# timer.net
KiCad netlist of a schematic drawn in EAGLE
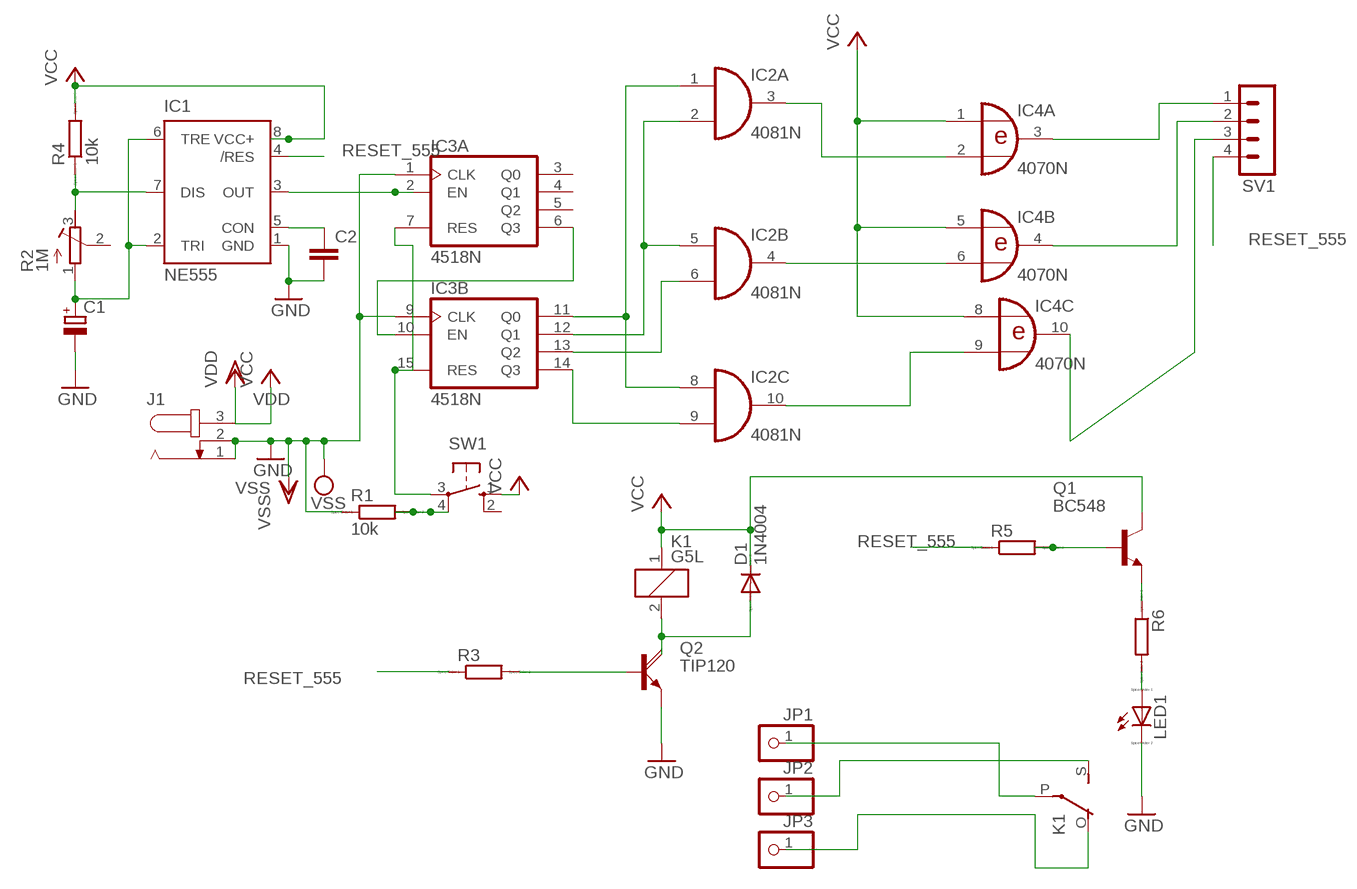
[diagram p0: schematic, sheet 1]

(export (version "E")
  (design (tool "Eeschema 10.0.6"))
  (components
    (comp (ref "C1")
      (value "CPOL-EUE2.5-6")
      (footprint "eagle-import:E2,5-6")
      (libsource (lib "eagle-import") (part "CPOL-EUE2.5-6"))
    )
    (comp (ref "C2")
      (value "C-EU025-024X044")
      (footprint "eagle-import:C025-024X044")
      (libsource (lib "eagle-import") (part "C-EU025-024X044"))
    )
    (comp (ref "D1")
      (value "1N4004")
      (footprint "eagle-import:DO41-10")
      (libsource (lib "eagle-import") (part "1N4004"))
    )
    (comp (ref "IC1")
      (value "NE555")
      (footprint "eagle-import:DIL-08")
      (fields (field (name "MF") "Arrow Electronics") (field (name "MPN") "NE555N"))
      (libsource (lib "eagle-import") (part "NE555"))
    )
    (comp (ref "IC2")
      (value "4081N")
      (footprint "eagle-import:DIL14")
      (libsource (lib "eagle-import") (part "4081N"))
    )
    (comp (ref "IC3")
      (value "4518N")
      (footprint "eagle-import:DIL16")
      (libsource (lib "eagle-import") (part "4518N"))
    )
    (comp (ref "IC4")
      (value "4070N")
      (footprint "eagle-import:DIL14")
      (libsource (lib "eagle-import") (part "4070N"))
    )
    (comp (ref "J1")
      (value "JACK-PLUG0")
      (footprint "eagle-import:SPC4077")
      (libsource (lib "eagle-import") (part "JACK-PLUG0"))
    )
    (comp (ref "JP1")
      (value "PINHD-1X1")
      (footprint "eagle-import:1X01")
      (libsource (lib "eagle-import") (part "PINHD-1X1"))
    )
    (comp (ref "JP2")
      (value "PINHD-1X1")
      (footprint "eagle-import:1X01")
      (libsource (lib "eagle-import") (part "PINHD-1X1"))
    )
    (comp (ref "JP3")
      (value "PINHD-1X1")
      (footprint "eagle-import:1X01")
      (libsource (lib "eagle-import") (part "PINHD-1X1"))
    )
    (comp (ref "K1")
      (value "G5L")
      (footprint "eagle-import:G5LE")
      (libsource (lib "eagle-import") (part "G5L"))
    )
    (comp (ref "LED1")
      (value "LED_ELD260")
      (footprint "eagle-import:LED_LD260")
      (libsource (lib "eagle-import") (part "LED_ELD260"))
    )
    (comp (ref "Q1")
      (value "BC548")
      (footprint "eagle-import:TO92-EBC")
      (libsource (lib "eagle-import") (part "BC548"))
    )
    (comp (ref "Q2")
      (value "TIP120")
      (footprint "eagle-import:TO220AH")
      (libsource (lib "eagle-import") (part "TIP120"))
    )
    (comp (ref "R1")
      (value "10k")
      (footprint "eagle-import:0207_10")
      (libsource (lib "eagle-import") (part "R0207/10"))
    )
    (comp (ref "R2")
      (value "1M")
      (footprint "eagle-import:RTRIM64W")
      (libsource (lib "eagle-import") (part "R-TRIMM64W"))
    )
    (comp (ref "R3")
      (value "R0207/10")
      (footprint "eagle-import:0207_10")
      (libsource (lib "eagle-import") (part "R0207/10"))
    )
    (comp (ref "R4")
      (value "10k")
      (footprint "eagle-import:0207_10")
      (libsource (lib "eagle-import") (part "R0207/10"))
    )
    (comp (ref "R5")
      (value "R0207/10")
      (footprint "eagle-import:0207_10")
      (libsource (lib "eagle-import") (part "R0207/10"))
    )
    (comp (ref "R6")
      (value "R0207/10")
      (footprint "eagle-import:0207_10")
      (libsource (lib "eagle-import") (part "R0207/10"))
    )
    (comp (ref "SV1")
      (value "MA04-1")
      (footprint "eagle-import:MA04-1")
      (libsource (lib "eagle-import") (part "MA04-1"))
    )
    (comp (ref "SW1")
      (value "10-XX")
      (footprint "eagle-import:B3F-10XX")
      (libsource (lib "eagle-import") (part "10-XX"))
    )
  )
  (nets
    (net (code "1") (name "/RESET_555") (class "Default")
      (node (ref "IC1") (pin "4") (pinfunction "/RES_4") (pintype "input"))
      (node (ref "R3") (pin "1") (pinfunction "1_1") (pintype "passive"))
      (node (ref "R5") (pin "1") (pinfunction "1_1") (pintype "passive"))
      (node (ref "SV1") (pin "4") (pinfunction "4_4") (pintype "passive"))
    )
    (net (code "2") (name "GND") (class "Default")
      (node (ref "C1") (pin "-") (pinfunction "-_-") (pintype "passive"))
      (node (ref "C2") (pin "2") (pinfunction "2_2") (pintype "passive"))
      (node (ref "IC1") (pin "1") (pinfunction "GND_1") (pintype "power_in"))
      (node (ref "IC3") (pin "1") (pinfunction "CLK_1") (pintype "input"))
      (node (ref "IC3") (pin "9") (pinfunction "CLK_9") (pintype "input"))
      (node (ref "J1") (pin "1") (pinfunction "1_1") (pintype "passive"))
      (node (ref "J1") (pin "2") (pinfunction "2_2") (pintype "passive"))
      (node (ref "LED1") (pin "K") (pinfunction "C_K") (pintype "passive"))
      (node (ref "Q2") (pin "E") (pinfunction "E_E") (pintype "passive"))
      (node (ref "R1") (pin "1") (pinfunction "1_1") (pintype "passive"))
    )
    (net (code "3") (name "Net-(D1-PadA)") (class "Default")
      (node (ref "D1") (pin "A") (pinfunction "A_A") (pintype "passive"))
      (node (ref "K1") (pin "2") (pinfunction "2_2") (pintype "passive"))
      (node (ref "Q2") (pin "C") (pinfunction "C_C") (pintype "passive"))
    )
    (net (code "4") (name "Net-(IC1-CON)") (class "Default")
      (node (ref "C2") (pin "1") (pinfunction "1_1") (pintype "passive"))
      (node (ref "IC1") (pin "5") (pinfunction "CON_5") (pintype "input"))
    )
    (net (code "5") (name "Net-(IC1-DIS)") (class "Default")
      (node (ref "IC1") (pin "7") (pinfunction "DIS_7") (pintype "input"))
      (node (ref "R2") (pin "3") (pinfunction "E_3") (pintype "passive"))
      (node (ref "R4") (pin "1") (pinfunction "1_1") (pintype "passive"))
    )
    (net (code "6") (name "Net-(IC1-OUT)") (class "Default")
      (node (ref "IC1") (pin "3") (pinfunction "OUT_3") (pintype "output"))
      (node (ref "IC3") (pin "2") (pinfunction "EN_2") (pintype "input"))
    )
    (net (code "7") (name "Net-(IC1-TRE)") (class "Default")
      (node (ref "C1") (pin "+") (pinfunction "+_+") (pintype "passive"))
      (node (ref "IC1") (pin "2") (pinfunction "TRI_2") (pintype "input"))
      (node (ref "IC1") (pin "6") (pinfunction "TRE_6") (pintype "input"))
      (node (ref "R2") (pin "1") (pinfunction "A_1") (pintype "passive"))
    )
    (net (code "8") (name "Net-(IC2A-I0)") (class "Default")
      (node (ref "IC2") (pin "1") (pinfunction "I0_1") (pintype "input"))
      (node (ref "IC2") (pin "8") (pinfunction "I0_8") (pintype "input"))
      (node (ref "IC3") (pin "11") (pinfunction "Q0_11") (pintype "output"))
    )
    (net (code "9") (name "Net-(IC2A-I1)") (class "Default")
      (node (ref "IC2") (pin "2") (pinfunction "I1_2") (pintype "input"))
      (node (ref "IC2") (pin "5") (pinfunction "I0_5") (pintype "input"))
      (node (ref "IC3") (pin "12") (pinfunction "Q1_12") (pintype "output"))
    )
    (net (code "10") (name "Net-(IC2A-O)") (class "Default")
      (node (ref "IC2") (pin "3") (pinfunction "O_3") (pintype "output"))
      (node (ref "IC4") (pin "2") (pinfunction "I1_2") (pintype "input"))
    )
    (net (code "11") (name "Net-(IC2B-I1)") (class "Default")
      (node (ref "IC2") (pin "6") (pinfunction "I1_6") (pintype "input"))
      (node (ref "IC3") (pin "13") (pinfunction "Q2_13") (pintype "output"))
    )
    (net (code "12") (name "Net-(IC2B-O)") (class "Default")
      (node (ref "IC2") (pin "4") (pinfunction "O_4") (pintype "output"))
      (node (ref "IC4") (pin "6") (pinfunction "I1_6") (pintype "input"))
    )
    (net (code "13") (name "Net-(IC2C-I1)") (class "Default")
      (node (ref "IC2") (pin "9") (pinfunction "I1_9") (pintype "input"))
      (node (ref "IC3") (pin "14") (pinfunction "Q3_14") (pintype "output"))
    )
    (net (code "14") (name "Net-(IC2C-O)") (class "Default")
      (node (ref "IC2") (pin "10") (pinfunction "O_10") (pintype "output"))
      (node (ref "IC4") (pin "9") (pinfunction "I1_9") (pintype "input"))
    )
    (net (code "15") (name "Net-(IC3A-Q3)") (class "Default")
      (node (ref "IC3") (pin "10") (pinfunction "EN_10") (pintype "input"))
      (node (ref "IC3") (pin "6") (pinfunction "Q3_6") (pintype "output"))
    )
    (net (code "16") (name "Net-(IC3A-RES)") (class "Default")
      (node (ref "IC3") (pin "15") (pinfunction "RES_15") (pintype "input"))
      (node (ref "IC3") (pin "7") (pinfunction "RES_7") (pintype "input"))
      (node (ref "SW1") (pin "3") (pinfunction "P_3") (pintype "passive"))
    )
    (net (code "17") (name "Net-(IC4A-O)") (class "Default")
      (node (ref "IC4") (pin "3") (pinfunction "O_3") (pintype "output"))
      (node (ref "SV1") (pin "1") (pinfunction "1_1") (pintype "passive"))
    )
    (net (code "18") (name "Net-(IC4B-O)") (class "Default")
      (node (ref "IC4") (pin "4") (pinfunction "O_4") (pintype "output"))
      (node (ref "SV1") (pin "2") (pinfunction "2_2") (pintype "passive"))
    )
    (net (code "19") (name "Net-(IC4C-O)") (class "Default")
      (node (ref "IC4") (pin "10") (pinfunction "O_10") (pintype "output"))
      (node (ref "SV1") (pin "3") (pinfunction "3_3") (pintype "passive"))
    )
    (net (code "20") (name "Net-(JP1-Pad1)") (class "Default")
      (node (ref "JP1") (pin "1") (pinfunction "1_1") (pintype "passive"))
      (node (ref "K1") (pin "P") (pinfunction "P_P") (pintype "passive"))
    )
    (net (code "21") (name "Net-(JP2-Pad1)") (class "Default")
      (node (ref "JP2") (pin "1") (pinfunction "1_1") (pintype "passive"))
      (node (ref "K1") (pin "S") (pinfunction "S_S") (pintype "passive"))
    )
    (net (code "22") (name "Net-(JP3-Pad1)") (class "Default")
      (node (ref "JP3") (pin "1") (pinfunction "1_1") (pintype "passive"))
      (node (ref "K1") (pin "O") (pinfunction "O_O") (pintype "passive"))
    )
    (net (code "23") (name "Net-(LED1-PadA)") (class "Default")
      (node (ref "LED1") (pin "A") (pinfunction "A_A") (pintype "passive"))
      (node (ref "R6") (pin "2") (pinfunction "2_2") (pintype "passive"))
    )
    (net (code "24") (name "Net-(Q1-PadB)") (class "Default")
      (node (ref "Q1") (pin "B") (pinfunction "B_B") (pintype "passive"))
      (node (ref "R5") (pin "2") (pinfunction "2_2") (pintype "passive"))
    )
    (net (code "25") (name "Net-(Q1-PadE)") (class "Default")
      (node (ref "Q1") (pin "E") (pinfunction "E_E") (pintype "passive"))
      (node (ref "R6") (pin "1") (pinfunction "1_1") (pintype "passive"))
    )
    (net (code "26") (name "Net-(Q2-PadB)") (class "Default")
      (node (ref "Q2") (pin "B") (pinfunction "B_B") (pintype "passive"))
      (node (ref "R3") (pin "2") (pinfunction "2_2") (pintype "passive"))
    )
    (net (code "27") (name "Net-(SW1-P1)") (class "Default")
      (node (ref "R1") (pin "2") (pinfunction "2_2") (pintype "passive"))
      (node (ref "SW1") (pin "4") (pinfunction "P1_4") (pintype "passive"))
    )
    (net (code "28") (name "VCC") (class "Default")
      (node (ref "D1") (pin "C") (pinfunction "C_C") (pintype "passive"))
      (node (ref "IC1") (pin "8") (pinfunction "VCC+_8") (pintype "power_in"))
      (node (ref "IC4") (pin "1") (pinfunction "I0_1") (pintype "input"))
      (node (ref "IC4") (pin "5") (pinfunction "I0_5") (pintype "input"))
      (node (ref "IC4") (pin "8") (pinfunction "I0_8") (pintype "input"))
      (node (ref "J1") (pin "3") (pinfunction "3_3") (pintype "passive"))
      (node (ref "K1") (pin "1") (pinfunction "1_1") (pintype "passive"))
      (node (ref "Q1") (pin "C") (pinfunction "C_C") (pintype "passive"))
      (node (ref "R4") (pin "2") (pinfunction "2_2") (pintype "passive"))
      (node (ref "SW1") (pin "1") (pinfunction "S_1") (pintype "passive"))
    )
    (net (code "29") (name "unconnected-(IC3A-Q0-Pad3)") (class "Default")
      (node (ref "IC3") (pin "3") (pinfunction "Q0_3") (pintype "output"))
    )
    (net (code "30") (name "unconnected-(IC3A-Q1-Pad4)") (class "Default")
      (node (ref "IC3") (pin "4") (pinfunction "Q1_4") (pintype "output"))
    )
    (net (code "31") (name "unconnected-(IC3A-Q2-Pad5)") (class "Default")
      (node (ref "IC3") (pin "5") (pinfunction "Q2_5") (pintype "output"))
    )
    (net (code "32") (name "unconnected-(R2-S-Pad2)") (class "Default")
      (node (ref "R2") (pin "2") (pinfunction "S_2") (pintype "passive"))
    )
    (net (code "33") (name "unconnected-(SW1-S1-Pad2)") (class "Default")
      (node (ref "SW1") (pin "2") (pinfunction "S1_2") (pintype "passive"))
    )
  )
)
